# ESP32_Pins.net
KiCad netlist of a schematic drawn in Altium Designer
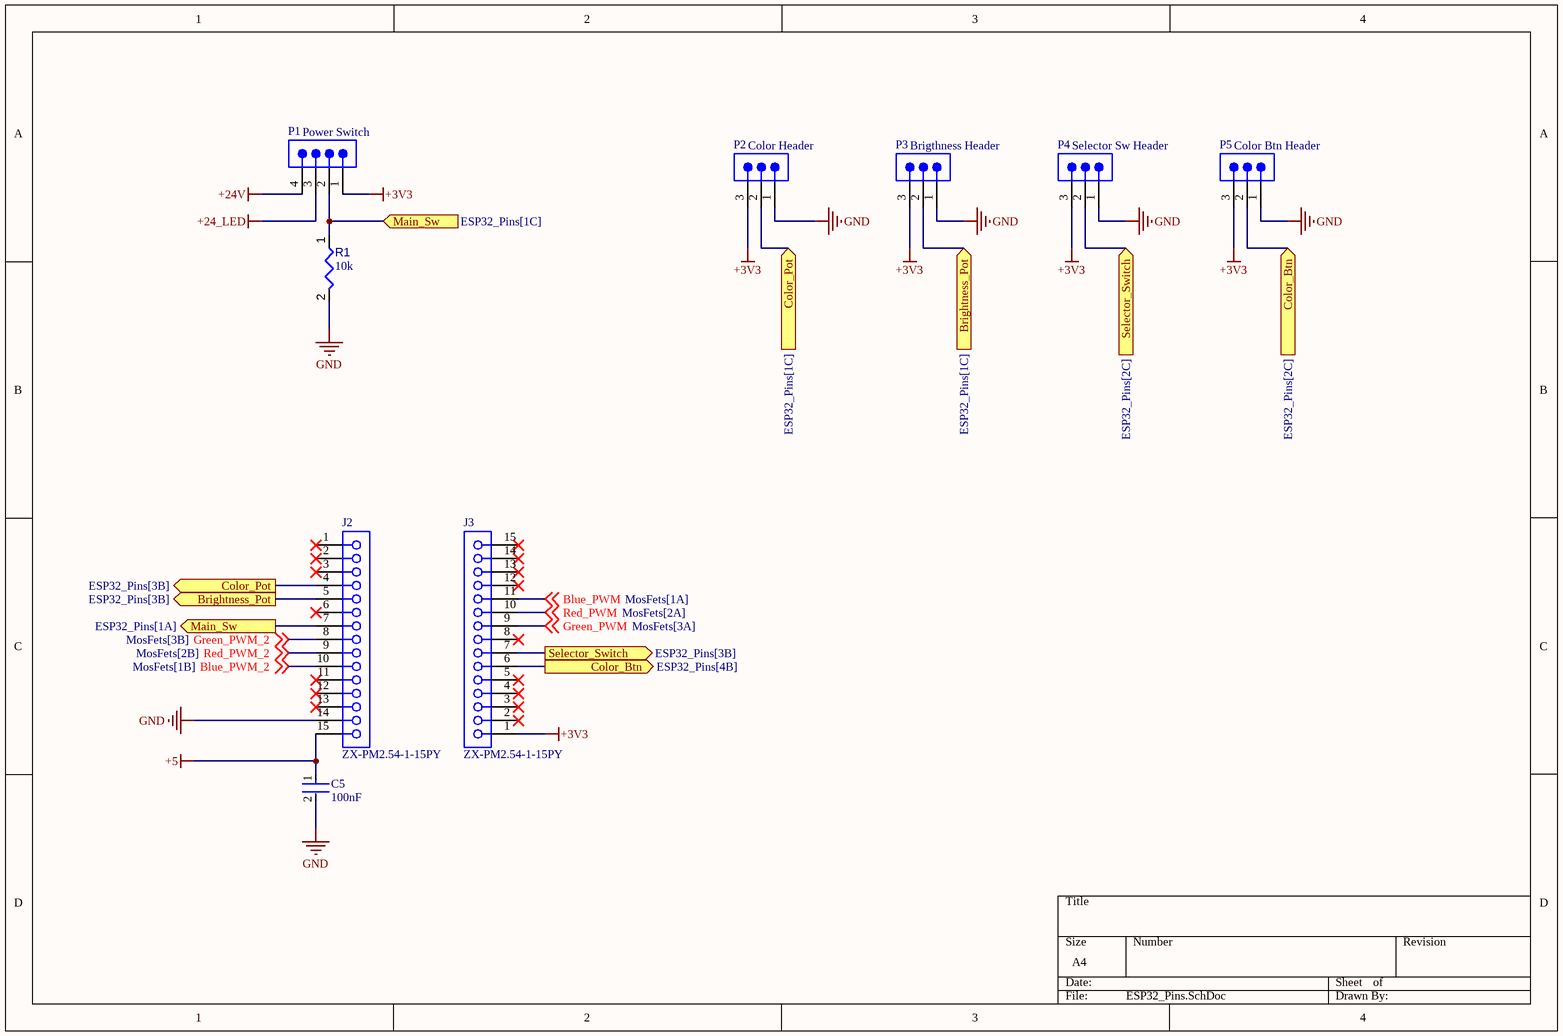
[diagram p0: ESP32_Pins.SchDoc]

(export (version "E")
  (design (tool "Eeschema 10.0.6"))
  (components
    (comp (ref "C5")
      (value "100nF")
      (footprint "FP-CC0603-DA-IPC_B")
      (description "Multilayer Ceramic Capacitor, CC Series, 0.1 - F, - 10%, X7R, 50 V, 0603 [1608 Metric]")
      (fields (field (name "VOLTAGE") "50V") (field (name "TOLERANCE") "10%"))
      (libsource (lib "Hood") (part "11868f565c42a9108669ba33697ecf6"))
    )
    (comp (ref "J2")
      (value "ZX-PM2.54-1-15PY")
      (footprint "68000-115HLF_MFG")
      (fields (field (name "MANUFACTURER") "Megastar") (field (name "JLCPCB PART #") "C7499333"))
      (libsource (lib "Hood") (part "SMTC-SSW-116-X-X-S-X"))
    )
    (comp (ref "J3")
      (value "ZX-PM2.54-1-15PY")
      (footprint "68000-115HLF_MFG")
      (fields (field (name "MANUFACTURER") "Megastar") (field (name "JLCPCB PART #") "C7499333"))
      (libsource (lib "Hood") (part "SMTC-SSW-116-X-X-S-X"))
    )
    (comp (ref "P1")
      (value "Power Switch")
      (footprint "SMTC-TSW-104-08-X-S")
      (description "Conn Unshrouded Header HDR 4 POS 2.54mm Solder ST Top Entry Thru-Hole Bulk")
      (libsource (lib "Hood") (part "SMTC-TSW-104-08-X-S"))
    )
    (comp (ref "P2")
      (value "Color Header")
      (footprint "FP-TSW-103-14-G-S-MFG")
      (description "Pin Header, Board-to-Board, 2.54 mm, 1 Rows, 3 Contacts, Through Hole, TSW")
      (libsource (lib "Hood") (part "Copy of SMTC-TSW-104-08-X-S"))
    )
    (comp (ref "P3")
      (value "Brigthness Header")
      (footprint "FP-TSW-103-14-G-S-MFG")
      (description "Pin Header, Board-to-Board, 2.54 mm, 1 Rows, 3 Contacts, Through Hole, TSW")
      (libsource (lib "Hood") (part "Copy of SMTC-TSW-104-08-X-S"))
    )
    (comp (ref "P4")
      (value "Selector Sw Header")
      (footprint "FP-TSW-103-14-G-S-MFG")
      (description "Pin Header, Board-to-Board, 2.54 mm, 1 Rows, 3 Contacts, Through Hole, TSW")
      (libsource (lib "Hood") (part "Copy of SMTC-TSW-104-08-X-S"))
    )
    (comp (ref "P5")
      (value "Color Btn Header")
      (footprint "FP-TSW-103-14-G-S-MFG")
      (description "Pin Header, Board-to-Board, 2.54 mm, 1 Rows, 3 Contacts, Through Hole, TSW")
      (libsource (lib "Hood") (part "Copy of SMTC-TSW-104-08-X-S"))
    )
    (comp (ref "R1")
      (value "10k")
      (footprint "FP-AC0603-IPC_C")
      (description "Res Thick Film 0603 10K Ohm 1% 0.1W(1/10W) ±100ppm/C Pad SMD")
      (fields (field (name "TOLERANCE") "5%") (field (name "Comment") "0603WAF1002T5E"))
      (libsource (lib "Hood") (part "RES-2"))
    )
  )
  (nets
    (net (code "1") (name "+3V3") (class "Default")
      (node (ref "J3") (pin "1") (pinfunction "1_1") (pintype "passive"))
      (node (ref "P1") (pin "1") (pinfunction "1_1") (pintype "passive"))
      (node (ref "P2") (pin "3") (pinfunction "3_3") (pintype "passive"))
      (node (ref "P3") (pin "3") (pinfunction "3_3") (pintype "passive"))
      (node (ref "P4") (pin "3") (pinfunction "3_3") (pintype "passive"))
      (node (ref "P5") (pin "3") (pinfunction "3_3") (pintype "passive"))
    )
    (net (code "2") (name "+5") (class "Default")
      (node (ref "C5") (pin "1") (pinfunction "1_1") (pintype "passive"))
      (node (ref "J2") (pin "15") (pinfunction "15_15") (pintype "passive"))
    )
    (net (code "3") (name "+24V") (class "Default")
      (node (ref "P1") (pin "4") (pinfunction "4_4") (pintype "passive"))
    )
    (net (code "4") (name "+24_LED") (class "Default")
      (node (ref "P1") (pin "3") (pinfunction "3_3") (pintype "passive"))
    )
    (net (code "5") (name "/Brightness_Pot") (class "Default")
      (node (ref "J2") (pin "5") (pinfunction "5_5") (pintype "passive"))
      (node (ref "P3") (pin "2") (pinfunction "2_2") (pintype "passive"))
    )
    (net (code "6") (name "/Color_Btn") (class "Default")
      (node (ref "J3") (pin "6") (pinfunction "6_6") (pintype "passive"))
      (node (ref "P5") (pin "2") (pinfunction "2_2") (pintype "passive"))
    )
    (net (code "7") (name "/Color_Pot") (class "Default")
      (node (ref "J2") (pin "4") (pinfunction "4_4") (pintype "passive"))
      (node (ref "P2") (pin "2") (pinfunction "2_2") (pintype "passive"))
    )
    (net (code "8") (name "/Main_Sw") (class "Default")
      (node (ref "J2") (pin "7") (pinfunction "7_7") (pintype "passive"))
      (node (ref "P1") (pin "2") (pinfunction "2_2") (pintype "passive"))
      (node (ref "R1") (pin "1") (pinfunction "1_1") (pintype "passive"))
    )
    (net (code "9") (name "/Selector_Switch") (class "Default")
      (node (ref "J3") (pin "7") (pinfunction "7_7") (pintype "passive"))
      (node (ref "P4") (pin "2") (pinfunction "2_2") (pintype "passive"))
    )
    (net (code "10") (name "Blue_PWM") (class "Default")
      (node (ref "J3") (pin "11") (pinfunction "11_11") (pintype "passive"))
    )
    (net (code "11") (name "Blue_PWM_2") (class "Default")
      (node (ref "J2") (pin "10") (pinfunction "10_10") (pintype "passive"))
    )
    (net (code "12") (name "GND") (class "Default")
      (node (ref "C5") (pin "2") (pinfunction "2_2") (pintype "passive"))
      (node (ref "J2") (pin "14") (pinfunction "14_14") (pintype "passive"))
      (node (ref "P2") (pin "1") (pinfunction "1_1") (pintype "passive"))
      (node (ref "P3") (pin "1") (pinfunction "1_1") (pintype "passive"))
      (node (ref "P4") (pin "1") (pinfunction "1_1") (pintype "passive"))
      (node (ref "P5") (pin "1") (pinfunction "1_1") (pintype "passive"))
      (node (ref "R1") (pin "2") (pinfunction "2_2") (pintype "passive"))
    )
    (net (code "13") (name "Green_PWM") (class "Default")
      (node (ref "J3") (pin "9") (pinfunction "9_9") (pintype "passive"))
    )
    (net (code "14") (name "Green_PWM_2") (class "Default")
      (node (ref "J2") (pin "8") (pinfunction "8_8") (pintype "passive"))
    )
    (net (code "15") (name "Red_PWM") (class "Default")
      (node (ref "J3") (pin "10") (pinfunction "10_10") (pintype "passive"))
    )
    (net (code "16") (name "Red_PWM_2") (class "Default")
      (node (ref "J2") (pin "9") (pinfunction "9_9") (pintype "passive"))
    )
    (net (code "17") (name "unconnected-(J2-Pad1)") (class "Default")
      (node (ref "J2") (pin "1") (pinfunction "1_1") (pintype "passive+no_connect"))
    )
    (net (code "18") (name "unconnected-(J2-Pad2)") (class "Default")
      (node (ref "J2") (pin "2") (pinfunction "2_2") (pintype "passive+no_connect"))
    )
    (net (code "19") (name "unconnected-(J2-Pad3)") (class "Default")
      (node (ref "J2") (pin "3") (pinfunction "3_3") (pintype "passive+no_connect"))
    )
    (net (code "20") (name "unconnected-(J2-Pad6)") (class "Default")
      (node (ref "J2") (pin "6") (pinfunction "6_6") (pintype "passive+no_connect"))
    )
    (net (code "21") (name "unconnected-(J2-Pad11)") (class "Default")
      (node (ref "J2") (pin "11") (pinfunction "11_11") (pintype "passive+no_connect"))
    )
    (net (code "22") (name "unconnected-(J2-Pad12)") (class "Default")
      (node (ref "J2") (pin "12") (pinfunction "12_12") (pintype "passive+no_connect"))
    )
    (net (code "23") (name "unconnected-(J2-Pad13)") (class "Default")
      (node (ref "J2") (pin "13") (pinfunction "13_13") (pintype "passive+no_connect"))
    )
    (net (code "24") (name "unconnected-(J3-Pad2)") (class "Default")
      (node (ref "J3") (pin "2") (pinfunction "2_2") (pintype "passive+no_connect"))
    )
    (net (code "25") (name "unconnected-(J3-Pad3)") (class "Default")
      (node (ref "J3") (pin "3") (pinfunction "3_3") (pintype "passive+no_connect"))
    )
    (net (code "26") (name "unconnected-(J3-Pad4)") (class "Default")
      (node (ref "J3") (pin "4") (pinfunction "4_4") (pintype "passive+no_connect"))
    )
    (net (code "27") (name "unconnected-(J3-Pad5)") (class "Default")
      (node (ref "J3") (pin "5") (pinfunction "5_5") (pintype "passive+no_connect"))
    )
    (net (code "28") (name "unconnected-(J3-Pad8)") (class "Default")
      (node (ref "J3") (pin "8") (pinfunction "8_8") (pintype "passive+no_connect"))
    )
    (net (code "29") (name "unconnected-(J3-Pad12)") (class "Default")
      (node (ref "J3") (pin "12") (pinfunction "12_12") (pintype "passive+no_connect"))
    )
    (net (code "30") (name "unconnected-(J3-Pad13)") (class "Default")
      (node (ref "J3") (pin "13") (pinfunction "13_13") (pintype "passive+no_connect"))
    )
    (net (code "31") (name "unconnected-(J3-Pad14)") (class "Default")
      (node (ref "J3") (pin "14") (pinfunction "14_14") (pintype "passive+no_connect"))
    )
    (net (code "32") (name "unconnected-(J3-Pad15)") (class "Default")
      (node (ref "J3") (pin "15") (pinfunction "15_15") (pintype "passive+no_connect"))
    )
  )
)
